# DVT-HPF-100kHz.net
KiCad netlist of a schematic drawn in Altium Designer
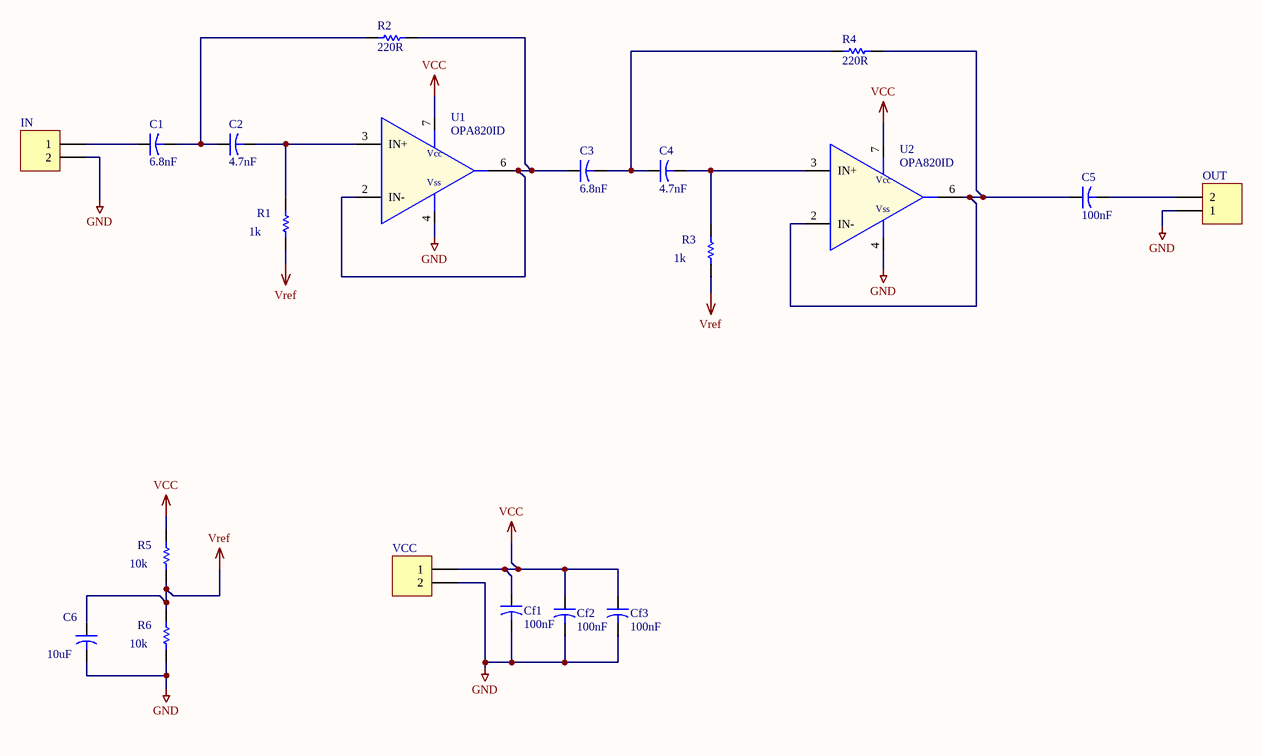
[diagram p0: DVT-HPF-100kHz.SchDoc]

(export (version "E")
  (design (tool "Eeschema 10.0.6"))
  (components
    (comp (ref "*") (value "Om") (footprint "Om-5mm") (libsource (lib "ICs") (part "Om")))
    (comp (ref "C1")
      (value "6.8nF")
      (footprint "Dummy-10mm")
      (description "Capacitor-Dummy-THT")
      (fields (field (name "PUBLISHER") "Sebastian Kulik"))
      (libsource (lib "Capacitors") (part "Capacitor-Dummy-THT"))
    )
    (comp (ref "C2")
      (value "4.7nF")
      (footprint "Dummy-10mm")
      (description "Capacitor-Dummy-THT")
      (fields (field (name "PUBLISHER") "Sebastian Kulik"))
      (libsource (lib "Capacitors") (part "Capacitor-Dummy-THT"))
    )
    (comp (ref "C3")
      (value "6.8nF")
      (footprint "Dummy-10mm")
      (description "Capacitor-Dummy-THT")
      (fields (field (name "PUBLISHER") "Sebastian Kulik"))
      (libsource (lib "Capacitors") (part "Capacitor-Dummy-THT"))
    )
    (comp (ref "C4")
      (value "4.7nF")
      (footprint "Dummy-10mm")
      (description "Capacitor-Dummy-THT")
      (fields (field (name "PUBLISHER") "Sebastian Kulik"))
      (libsource (lib "Capacitors") (part "Capacitor-Dummy-THT"))
    )
    (comp (ref "C5")
      (value "100nF")
      (footprint "Dummy-10mm")
      (description "Capacitor-Dummy-THT")
      (fields (field (name "PUBLISHER") "Sebastian Kulik"))
      (libsource (lib "Capacitors") (part "Capacitor-Dummy-THT"))
    )
    (comp (ref "C6")
      (value "10uF")
      (footprint "Dummy-10mm")
      (description "Capacitor-Dummy-THT")
      (fields (field (name "PUBLISHER") "Sebastian Kulik"))
      (libsource (lib "Capacitors") (part "Capacitor-Dummy-THT"))
    )
    (comp (ref "Cf1")
      (value "100nF")
      (footprint "Dummy-10mm")
      (description "Capacitor-Dummy-THT")
      (fields (field (name "PUBLISHER") "Sebastian Kulik"))
      (libsource (lib "Capacitors") (part "Capacitor-Dummy-THT"))
    )
    (comp (ref "Cf2")
      (value "100nF")
      (footprint "Dummy-10mm")
      (description "Capacitor-Dummy-THT")
      (fields (field (name "PUBLISHER") "Sebastian Kulik"))
      (libsource (lib "Capacitors") (part "Capacitor-Dummy-THT"))
    )
    (comp (ref "Cf3")
      (value "100nF")
      (footprint "Dummy-10mm")
      (description "Capacitor-Dummy-THT")
      (fields (field (name "PUBLISHER") "Sebastian Kulik"))
      (libsource (lib "Capacitors") (part "Capacitor-Dummy-THT"))
    )
    (comp (ref "IN")
      (value "PHOENIX_1715721")
      (footprint "Phoenix-2-5_08")
      (description "Phoenix, 2 pol, 5.08mm, 22A, 715721")
      (fields (field (name "MANUFACTURER") "Phoenix") (field (name "PUBLISHER") "Sebastian Kulik"))
      (libsource (lib "") (part "2Pol_1715721_1"))
    )
    (comp (ref "OUT")
      (value "PHOENIX_1715721")
      (footprint "Phoenix-2-5_08")
      (description "Phoenix, 2 pol, 5.08mm, 22A, 715721")
      (fields (field (name "MANUFACTURER") "Phoenix") (field (name "PUBLISHER") "Sebastian Kulik"))
      (libsource (lib "Connectors") (part "2Pol_1715721"))
    )
    (comp (ref "R1")
      (value "1k")
      (footprint "Dummy-10mm")
      (description "Resistor-Dummy-THT")
      (fields (field (name "PUBLISHER") "Sebastian Kulik"))
      (libsource (lib "Resistors") (part "Resistor-Dummy-THT"))
    )
    (comp (ref "R2")
      (value "220R")
      (footprint "Dummy-10mm")
      (description "Resistor-Dummy-THT")
      (fields (field (name "PUBLISHER") "Sebastian Kulik"))
      (libsource (lib "Resistors") (part "Resistor-Dummy-THT"))
    )
    (comp (ref "R3")
      (value "1k")
      (footprint "Dummy-10mm")
      (description "Resistor-Dummy-THT")
      (fields (field (name "PUBLISHER") "Sebastian Kulik"))
      (libsource (lib "Resistors") (part "Resistor-Dummy-THT"))
    )
    (comp (ref "R4")
      (value "220R")
      (footprint "Dummy-10mm")
      (description "Resistor-Dummy-THT")
      (fields (field (name "PUBLISHER") "Sebastian Kulik"))
      (libsource (lib "Resistors") (part "Resistor-Dummy-THT"))
    )
    (comp (ref "R5")
      (value "10k")
      (footprint "Dummy-10mm")
      (description "Resistor-Dummy-THT")
      (fields (field (name "PUBLISHER") "Sebastian Kulik"))
      (libsource (lib "Resistors") (part "Resistor-Dummy-THT"))
    )
    (comp (ref "R6")
      (value "10k")
      (footprint "Dummy-10mm")
      (description "Resistor-Dummy-THT")
      (fields (field (name "PUBLISHER") "Sebastian Kulik"))
      (libsource (lib "Resistors") (part "Resistor-Dummy-THT"))
    )
    (comp (ref "U1")
      (value "OPA820ID")
      (footprint "SOP8_L")
      (description "High speed OP, 260MHz")
      (fields (field (name "MANUFACTURER") "TI") (field (name "PUBLISHER") "Sebastian Kulik"))
      (libsource (lib "ICs") (part "OPA820ID"))
    )
    (comp (ref "U2")
      (value "OPA820ID")
      (footprint "SOP8_L")
      (description "High speed OP, 260MHz")
      (fields (field (name "MANUFACTURER") "TI") (field (name "PUBLISHER") "Sebastian Kulik"))
      (libsource (lib "ICs") (part "OPA820ID"))
    )
    (comp (ref "VCC")
      (value "PHOENIX_1715721")
      (footprint "Phoenix-2-5_08")
      (description "Phoenix, 2 pol, 5.08mm, 22A, 715721")
      (fields (field (name "MANUFACTURER") "Phoenix") (field (name "PUBLISHER") "Sebastian Kulik"))
      (libsource (lib "") (part "2Pol_1715721_1"))
    )
  )
  (nets
    (net (code "1") (name "GND") (class "Default")
      (node (ref "C6") (pin "2") (pinfunction "2_2") (pintype "passive"))
      (node (ref "Cf1") (pin "2") (pinfunction "2_2") (pintype "passive"))
      (node (ref "Cf2") (pin "2") (pinfunction "2_2") (pintype "passive"))
      (node (ref "Cf3") (pin "2") (pinfunction "2_2") (pintype "passive"))
      (node (ref "IN") (pin "2") (pinfunction "2_2") (pintype "passive"))
      (node (ref "OUT") (pin "1") (pinfunction "1_1") (pintype "passive"))
      (node (ref "R6") (pin "1") (pinfunction "1_1") (pintype "passive"))
      (node (ref "U1") (pin "4") (pinfunction "Vss_4") (pintype "passive"))
      (node (ref "U2") (pin "4") (pinfunction "Vss_4") (pintype "passive"))
      (node (ref "VCC") (pin "2") (pinfunction "2_2") (pintype "passive"))
    )
    (net (code "2") (name "Net-(C1-Pad1)") (class "Default")
      (node (ref "C1") (pin "1") (pinfunction "1_1") (pintype "passive"))
      (node (ref "IN") (pin "1") (pinfunction "1_1") (pintype "passive"))
    )
    (net (code "3") (name "Net-(C1-Pad2)") (class "Default")
      (node (ref "C1") (pin "2") (pinfunction "2_2") (pintype "passive"))
      (node (ref "C2") (pin "1") (pinfunction "1_1") (pintype "passive"))
      (node (ref "R2") (pin "2") (pinfunction "2_2") (pintype "passive"))
    )
    (net (code "4") (name "Net-(C3-Pad2)") (class "Default")
      (node (ref "C3") (pin "2") (pinfunction "2_2") (pintype "passive"))
      (node (ref "C4") (pin "1") (pinfunction "1_1") (pintype "passive"))
      (node (ref "R4") (pin "2") (pinfunction "2_2") (pintype "passive"))
    )
    (net (code "5") (name "Net-(C5-Pad2)") (class "Default")
      (node (ref "C5") (pin "2") (pinfunction "2_2") (pintype "passive"))
      (node (ref "OUT") (pin "2") (pinfunction "2_2") (pintype "passive"))
    )
    (net (code "6") (name "Net-(U1-IN+)") (class "Default")
      (node (ref "C2") (pin "2") (pinfunction "2_2") (pintype "passive"))
      (node (ref "R1") (pin "2") (pinfunction "2_2") (pintype "passive"))
      (node (ref "U1") (pin "3") (pinfunction "IN+_3") (pintype "power_in"))
    )
    (net (code "7") (name "Net-(U1-IN-)") (class "Default")
      (node (ref "C3") (pin "1") (pinfunction "1_1") (pintype "passive"))
      (node (ref "R2") (pin "1") (pinfunction "1_1") (pintype "passive"))
      (node (ref "U1") (pin "2") (pinfunction "IN-_2") (pintype "passive"))
      (node (ref "U1") (pin "6") (pinfunction "OUT_6") (pintype "passive"))
    )
    (net (code "8") (name "Net-(U2-IN+)") (class "Default")
      (node (ref "C4") (pin "2") (pinfunction "2_2") (pintype "passive"))
      (node (ref "R3") (pin "2") (pinfunction "2_2") (pintype "passive"))
      (node (ref "U2") (pin "3") (pinfunction "IN+_3") (pintype "power_in"))
    )
    (net (code "9") (name "Net-(U2-IN-)") (class "Default")
      (node (ref "C5") (pin "1") (pinfunction "1_1") (pintype "passive"))
      (node (ref "R4") (pin "1") (pinfunction "1_1") (pintype "passive"))
      (node (ref "U2") (pin "2") (pinfunction "IN-_2") (pintype "passive"))
      (node (ref "U2") (pin "6") (pinfunction "OUT_6") (pintype "passive"))
    )
    (net (code "10") (name "VCC") (class "Default")
      (node (ref "Cf1") (pin "1") (pinfunction "1_1") (pintype "passive"))
      (node (ref "Cf2") (pin "1") (pinfunction "1_1") (pintype "passive"))
      (node (ref "Cf3") (pin "1") (pinfunction "1_1") (pintype "passive"))
      (node (ref "R5") (pin "2") (pinfunction "2_2") (pintype "passive"))
      (node (ref "U1") (pin "7") (pinfunction "Vcc_7") (pintype "passive"))
      (node (ref "U2") (pin "7") (pinfunction "Vcc_7") (pintype "passive"))
      (node (ref "VCC") (pin "1") (pinfunction "1_1") (pintype "passive"))
    )
    (net (code "11") (name "Vref") (class "Default")
      (node (ref "C6") (pin "1") (pinfunction "1_1") (pintype "passive"))
      (node (ref "R1") (pin "1") (pinfunction "1_1") (pintype "passive"))
      (node (ref "R3") (pin "1") (pinfunction "1_1") (pintype "passive"))
      (node (ref "R5") (pin "1") (pinfunction "1_1") (pintype "passive"))
      (node (ref "R6") (pin "2") (pinfunction "2_2") (pintype "passive"))
    )
  )
)
